# powersupply.net
KiCad netlist of a schematic drawn in Altium Designer
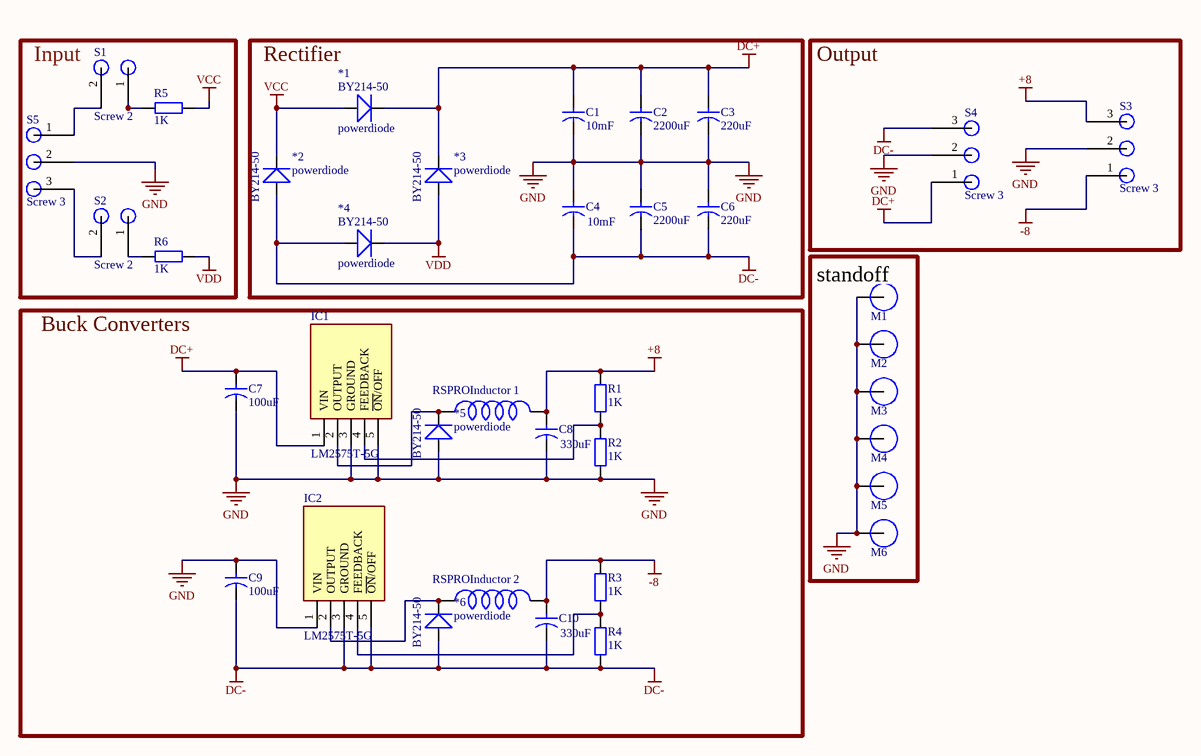
[diagram p0: powersupply.SchDoc]

(export (version "E")
  (design (tool "Eeschema 10.0.6"))
  (components
    (comp (ref "*1")
      (value "powerdiode")
      (footprint "BY214-50")
      (description "50V/6A Powerdiode")
      (libsource (lib "AAURacing") (part "powerdiode"))
    )
    (comp (ref "*2")
      (value "powerdiode")
      (footprint "BY214-50")
      (description "50V/6A Powerdiode")
      (libsource (lib "AAURacing") (part "powerdiode"))
    )
    (comp (ref "*3")
      (value "powerdiode")
      (footprint "BY214-50")
      (description "50V/6A Powerdiode")
      (libsource (lib "AAURacing") (part "powerdiode"))
    )
    (comp (ref "*4")
      (value "powerdiode")
      (footprint "BY214-50")
      (description "50V/6A Powerdiode")
      (libsource (lib "AAURacing") (part "powerdiode"))
    )
    (comp (ref "*5")
      (value "powerdiode")
      (footprint "BY214-50")
      (description "50V/6A Powerdiode")
      (libsource (lib "AAURacing") (part "powerdiode"))
    )
    (comp (ref "*6")
      (value "powerdiode")
      (footprint "BY214-50")
      (description "50V/6A Powerdiode")
      (libsource (lib "AAURacing") (part "powerdiode"))
    )
    (comp (ref "1")
      (value "RSPROInductor")
      (footprint "RS PRO inductor")
      (libsource (lib "esd410") (part "homemade inductor"))
    )
    (comp (ref "2")
      (value "RSPROInductor")
      (footprint "RS PRO inductor")
      (libsource (lib "esd410") (part "homemade inductor"))
    )
    (comp (ref "C1")
      (value "Cap")
      (footprint "Cap Lyt Ø30")
      (fields (field (name "CAPACITY") "10mF"))
      (libsource (lib "AAURacing") (part "Capacitor electrolytic"))
    )
    (comp (ref "C2")
      (value "Cap")
      (footprint "Cap Lyt Ø18")
      (fields (field (name "CAPACITY") "2200uF"))
      (libsource (lib "AAURacing") (part "Capacitor electrolytic"))
    )
    (comp (ref "C3")
      (value "Cap")
      (footprint "Cap Lyt Ø8")
      (fields (field (name "CAPACITY") "220uF"))
      (libsource (lib "AAURacing") (part "Capacitor electrolytic"))
    )
    (comp (ref "C4")
      (value "Cap")
      (footprint "Cap Lyt Ø30")
      (fields (field (name "CAPACITY") "10mF"))
      (libsource (lib "AAURacing") (part "Capacitor electrolytic"))
    )
    (comp (ref "C5")
      (value "Cap")
      (footprint "Cap Lyt Ø18")
      (fields (field (name "CAPACITY") "2200uF"))
      (libsource (lib "AAURacing") (part "Capacitor electrolytic"))
    )
    (comp (ref "C6")
      (value "Cap")
      (footprint "Cap Lyt Ø8")
      (fields (field (name "CAPACITY") "220uF"))
      (libsource (lib "AAURacing") (part "Capacitor electrolytic"))
    )
    (comp (ref "C7")
      (value "Cap")
      (footprint "Cap Lyt Ø8")
      (fields (field (name "CAPACITY") "100uF"))
      (libsource (lib "AAURacing") (part "Capacitor electrolytic"))
    )
    (comp (ref "C8")
      (value "Cap")
      (footprint "Cap Lyt Ø8")
      (fields (field (name "CAPACITY") "330uF"))
      (libsource (lib "AAURacing") (part "Capacitor electrolytic"))
    )
    (comp (ref "C9")
      (value "Cap")
      (footprint "Cap Lyt Ø8")
      (fields (field (name "CAPACITY") "100uF"))
      (libsource (lib "AAURacing") (part "Capacitor electrolytic"))
    )
    (comp (ref "C10")
      (value "Cap")
      (footprint "Cap Lyt Ø8")
      (fields (field (name "CAPACITY") "330uF"))
      (libsource (lib "AAURacing") (part "Capacitor electrolytic"))
    )
    (comp (ref "IC1")
      (value "LM2575T-5G")
      (footprint "SamacSys:LM2575T5G")
      (description "Integrated Circuit")
      (fields (field (name "MOUSER PART NUMBER") "863-LM2575T-5G"))
      (libsource (lib "*") (part "LM2575T-5G"))
    )
    (comp (ref "IC2")
      (value "LM2575T-5G")
      (footprint "SamacSys:LM2575T5G")
      (description "Integrated Circuit")
      (fields (field (name "MOUSER PART NUMBER") "863-LM2575T-5G"))
      (libsource (lib "*") (part "LM2575T-5G"))
    )
    (comp (ref "M1")
      (value "Screw Hole")
      (footprint "M3 Hole")
      (libsource (lib "AAURacing") (part "Screw Hole"))
    )
    (comp (ref "M2")
      (value "Screw Hole")
      (footprint "M3 Hole")
      (libsource (lib "AAURacing") (part "Screw Hole"))
    )
    (comp (ref "M3")
      (value "Screw Hole")
      (footprint "M3 Hole")
      (libsource (lib "AAURacing") (part "Screw Hole"))
    )
    (comp (ref "M4")
      (value "Screw Hole")
      (footprint "M3 Hole")
      (libsource (lib "AAURacing") (part "Screw Hole"))
    )
    (comp (ref "M5")
      (value "Screw Hole")
      (footprint "M3 Hole")
      (libsource (lib "AAURacing") (part "Screw Hole"))
    )
    (comp (ref "M6")
      (value "Screw Hole")
      (footprint "M3 Hole")
      (libsource (lib "AAURacing") (part "Screw Hole"))
    )
    (comp (ref "R1")
      (value "Resistor")
      (footprint "RES THT 9mm")
      (fields (field (name "OHM") "1K"))
      (libsource (lib "AAURacing") (part "Resistor"))
    )
    (comp (ref "R2")
      (value "Resistor")
      (footprint "RES THT 9mm")
      (fields (field (name "OHM") "1K"))
      (libsource (lib "AAURacing") (part "Resistor"))
    )
    (comp (ref "R3")
      (value "Resistor")
      (footprint "RES THT 9mm")
      (fields (field (name "OHM") "1K"))
      (libsource (lib "AAURacing") (part "Resistor"))
    )
    (comp (ref "R4")
      (value "Resistor")
      (footprint "RES THT 9mm")
      (fields (field (name "OHM") "1K"))
      (libsource (lib "AAURacing") (part "Resistor"))
    )
    (comp (ref "R5")
      (value "Resistor")
      (footprint "RES THT 9mm")
      (fields (field (name "OHM") "1K"))
      (libsource (lib "AAURacing") (part "Resistor"))
    )
    (comp (ref "R6")
      (value "Resistor")
      (footprint "RES THT 9mm")
      (fields (field (name "OHM") "1K"))
      (libsource (lib "AAURacing") (part "Resistor"))
    )
    (comp (ref "S1") (value "Screw 2") (footprint "Screw-2") (libsource (lib "AAURacing") (part "Screw 2")))
    (comp (ref "S2") (value "Screw 2") (footprint "Screw-2") (libsource (lib "AAURacing") (part "Screw 2")))
    (comp (ref "S3") (value "Screw 3") (footprint "Screw-3") (libsource (lib "AAURacing") (part "Screw 3")))
    (comp (ref "S4") (value "Screw 3") (footprint "Screw-3") (libsource (lib "AAURacing") (part "Screw 3")))
    (comp (ref "S5") (value "Screw 3") (footprint "Screw-3") (libsource (lib "AAURacing") (part "Screw 3")))
  )
  (nets
    (net (code "1") (name "+8") (class "Default")
      (node (ref "1") (pin "2") (pintype "passive"))
      (node (ref "C8") (pin "1") (pinfunction "1_1") (pintype "passive"))
      (node (ref "R1") (pin "2") (pinfunction "2_2") (pintype "passive"))
      (node (ref "S3") (pin "3") (pinfunction "3_3") (pintype "passive"))
    )
    (net (code "2") (name "-8") (class "Default")
      (node (ref "2") (pin "2") (pintype "passive"))
      (node (ref "C10") (pin "1") (pinfunction "1_1") (pintype "passive"))
      (node (ref "R3") (pin "2") (pinfunction "2_2") (pintype "passive"))
      (node (ref "S3") (pin "1") (pinfunction "1_1") (pintype "passive"))
    )
    (net (code "3") (name "DC+") (class "Default")
      (node (ref "*1") (pin "2") (pinfunction "2_2") (pintype "passive"))
      (node (ref "*3") (pin "2") (pinfunction "2_2") (pintype "passive"))
      (node (ref "C1") (pin "1") (pinfunction "1_1") (pintype "passive"))
      (node (ref "C2") (pin "1") (pinfunction "1_1") (pintype "passive"))
      (node (ref "C3") (pin "1") (pinfunction "1_1") (pintype "passive"))
      (node (ref "C7") (pin "1") (pinfunction "1_1") (pintype "passive"))
      (node (ref "IC1") (pin "1") (pinfunction "VIN_1") (pintype "passive"))
      (node (ref "S4") (pin "1") (pinfunction "1_1") (pintype "passive"))
    )
    (net (code "4") (name "DC-") (class "Default")
      (node (ref "*2") (pin "1") (pinfunction "1_1") (pintype "passive"))
      (node (ref "*4") (pin "1") (pinfunction "1_1") (pintype "passive"))
      (node (ref "*6") (pin "1") (pinfunction "1_1") (pintype "passive"))
      (node (ref "C10") (pin "2") (pinfunction "g_2") (pintype "passive"))
      (node (ref "C4") (pin "2") (pinfunction "g_2") (pintype "passive"))
      (node (ref "C5") (pin "2") (pinfunction "g_2") (pintype "passive"))
      (node (ref "C6") (pin "2") (pinfunction "g_2") (pintype "passive"))
      (node (ref "C9") (pin "2") (pinfunction "g_2") (pintype "passive"))
      (node (ref "IC2") (pin "3") (pinfunction "GROUND_3") (pintype "passive"))
      (node (ref "IC2") (pin "5") (pinfunction "~{ON}/OFF_5") (pintype "passive"))
      (node (ref "R4") (pin "1") (pinfunction "1_1") (pintype "passive"))
      (node (ref "S4") (pin "3") (pinfunction "3_3") (pintype "passive"))
    )
    (net (code "5") (name "GND") (class "Default")
      (node (ref "*5") (pin "1") (pinfunction "1_1") (pintype "passive"))
      (node (ref "C1") (pin "2") (pinfunction "g_2") (pintype "passive"))
      (node (ref "C2") (pin "2") (pinfunction "g_2") (pintype "passive"))
      (node (ref "C3") (pin "2") (pinfunction "g_2") (pintype "passive"))
      (node (ref "C4") (pin "1") (pinfunction "1_1") (pintype "passive"))
      (node (ref "C5") (pin "1") (pinfunction "1_1") (pintype "passive"))
      (node (ref "C6") (pin "1") (pinfunction "1_1") (pintype "passive"))
      (node (ref "C7") (pin "2") (pinfunction "g_2") (pintype "passive"))
      (node (ref "C8") (pin "2") (pinfunction "g_2") (pintype "passive"))
      (node (ref "C9") (pin "1") (pinfunction "1_1") (pintype "passive"))
      (node (ref "IC1") (pin "3") (pinfunction "GROUND_3") (pintype "passive"))
      (node (ref "IC1") (pin "5") (pinfunction "~{ON}/OFF_5") (pintype "passive"))
      (node (ref "IC2") (pin "1") (pinfunction "VIN_1") (pintype "passive"))
      (node (ref "M1") (pin "1") (pinfunction "1_1") (pintype "passive"))
      (node (ref "M2") (pin "1") (pinfunction "1_1") (pintype "passive"))
      (node (ref "M3") (pin "1") (pinfunction "1_1") (pintype "passive"))
      (node (ref "M4") (pin "1") (pinfunction "1_1") (pintype "passive"))
      (node (ref "M5") (pin "1") (pinfunction "1_1") (pintype "passive"))
      (node (ref "M6") (pin "1") (pinfunction "1_1") (pintype "passive"))
      (node (ref "R2") (pin "1") (pinfunction "1_1") (pintype "passive"))
      (node (ref "S3") (pin "2") (pinfunction "2_2") (pintype "passive"))
      (node (ref "S4") (pin "2") (pinfunction "2_2") (pintype "passive"))
      (node (ref "S5") (pin "2") (pinfunction "2_2") (pintype "passive"))
    )
    (net (code "6") (name "Net-(IC1-FEEDBACK)") (class "Default")
      (node (ref "IC1") (pin "4") (pinfunction "FEEDBACK_4") (pintype "passive"))
      (node (ref "R1") (pin "1") (pinfunction "1_1") (pintype "passive"))
      (node (ref "R2") (pin "2") (pinfunction "2_2") (pintype "passive"))
    )
    (net (code "7") (name "Net-(IC1-OUTPUT)") (class "Default")
      (node (ref "*5") (pin "2") (pinfunction "2_2") (pintype "passive"))
      (node (ref "1") (pin "1") (pintype "passive"))
      (node (ref "IC1") (pin "2") (pinfunction "OUTPUT_2") (pintype "passive"))
    )
    (net (code "8") (name "Net-(IC2-FEEDBACK)") (class "Default")
      (node (ref "IC2") (pin "4") (pinfunction "FEEDBACK_4") (pintype "passive"))
      (node (ref "R3") (pin "1") (pinfunction "1_1") (pintype "passive"))
      (node (ref "R4") (pin "2") (pinfunction "2_2") (pintype "passive"))
    )
    (net (code "9") (name "Net-(IC2-OUTPUT)") (class "Default")
      (node (ref "*6") (pin "2") (pinfunction "2_2") (pintype "passive"))
      (node (ref "2") (pin "1") (pintype "passive"))
      (node (ref "IC2") (pin "2") (pinfunction "OUTPUT_2") (pintype "passive"))
    )
    (net (code "10") (name "Net-(R5-Pad2)") (class "Default")
      (node (ref "R5") (pin "2") (pinfunction "2_2") (pintype "passive"))
      (node (ref "S1") (pin "1") (pinfunction "1_1") (pintype "passive"))
    )
    (net (code "11") (name "Net-(R6-Pad2)") (class "Default")
      (node (ref "R6") (pin "2") (pinfunction "2_2") (pintype "passive"))
      (node (ref "S2") (pin "1") (pinfunction "1_1") (pintype "passive"))
    )
    (net (code "12") (name "Net-(S1-Pad2)") (class "Default")
      (node (ref "S1") (pin "2") (pinfunction "2_2") (pintype "passive"))
      (node (ref "S5") (pin "1") (pinfunction "1_1") (pintype "passive"))
    )
    (net (code "13") (name "Net-(S2-Pad2)") (class "Default")
      (node (ref "S2") (pin "2") (pinfunction "2_2") (pintype "passive"))
      (node (ref "S5") (pin "3") (pinfunction "3_3") (pintype "passive"))
    )
    (net (code "14") (name "VCC") (class "Default")
      (node (ref "*1") (pin "1") (pinfunction "1_1") (pintype "passive"))
      (node (ref "*2") (pin "2") (pinfunction "2_2") (pintype "passive"))
      (node (ref "R5") (pin "1") (pinfunction "1_1") (pintype "passive"))
    )
    (net (code "15") (name "VDD") (class "Default")
      (node (ref "*3") (pin "1") (pinfunction "1_1") (pintype "passive"))
      (node (ref "*4") (pin "2") (pinfunction "2_2") (pintype "passive"))
      (node (ref "R6") (pin "1") (pinfunction "1_1") (pintype "passive"))
    )
  )
)
